# Joystick_Board.net
KiCad netlist of a schematic drawn in Altium Designer
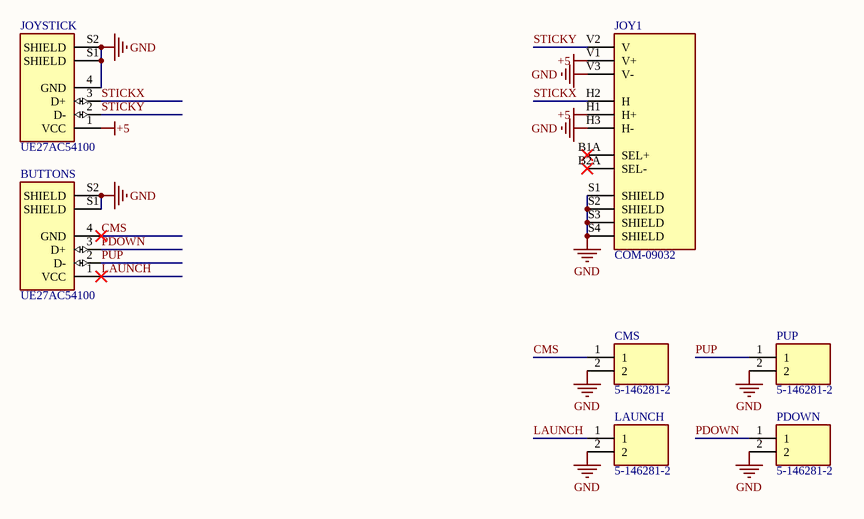
[diagram p0: Joystick Board.SchDoc]

(export (version "E")
  (design (tool "Eeschema 10.0.6"))
  (components
    (comp (ref "BUTTONS")
      (value "UE27AC54100")
      (footprint "AMPHENOL_UE27AC54100")
      (description "USB-A _USB TYPE-A_ USB 2.0 Receptacle Connector 4 Position Through Hole, Right Angle")
      (fields
        (field (name "MF") "Amphenol ICC _Commercial Products_")
        (field (name "DIGI-KEY_PART_NUMBER") "UE27AC54100-ND")
      )
      (libsource (lib "UE27AC54100") (part "UE27AC54100"))
    )
    (comp (ref "CMS")
      (value "5-146281-2")
      (footprint "TE_5-146281-2")
      (description "Header; Breakaway; 0.100 in.; PC Board; Single; 2; 0.025 in.; 0.12 in.; 3 A")
      (fields (field (name "MF") "TE Connectivity"))
      (libsource (lib "5-146281-2") (part "5-146281-2"))
    )
    (comp (ref "JOY1")
      (value "COM-09032")
      (footprint "XDCR_COM-09032")
      (description "Thumb Joystick")
      (libsource (lib "COM-09032") (part "COM-09032"))
    )
    (comp (ref "JOYSTICK")
      (value "UE27AC54100")
      (footprint "AMPHENOL_UE27AC54100")
      (description "USB-A _USB TYPE-A_ USB 2.0 Receptacle Connector 4 Position Through Hole, Right Angle")
      (fields
        (field (name "MF") "Amphenol ICC _Commercial Products_")
        (field (name "DIGI-KEY_PART_NUMBER") "UE27AC54100-ND")
      )
      (libsource (lib "UE27AC54100") (part "UE27AC54100"))
    )
    (comp (ref "LAUNCH")
      (value "5-146281-2")
      (footprint "TE_5-146281-2")
      (description "Header; Breakaway; 0.100 in.; PC Board; Single; 2; 0.025 in.; 0.12 in.; 3 A")
      (fields (field (name "MF") "TE Connectivity"))
      (libsource (lib "5-146281-2") (part "5-146281-2"))
    )
    (comp (ref "PDOWN")
      (value "5-146281-2")
      (footprint "TE_5-146281-2")
      (description "Header; Breakaway; 0.100 in.; PC Board; Single; 2; 0.025 in.; 0.12 in.; 3 A")
      (fields (field (name "MF") "TE Connectivity"))
      (libsource (lib "5-146281-2") (part "5-146281-2"))
    )
    (comp (ref "PUP")
      (value "5-146281-2")
      (footprint "TE_5-146281-2")
      (description "Header; Breakaway; 0.100 in.; PC Board; Single; 2; 0.025 in.; 0.12 in.; 3 A")
      (fields (field (name "MF") "TE Connectivity"))
      (libsource (lib "5-146281-2") (part "5-146281-2"))
    )
  )
  (nets
    (net (code "1") (name "+5") (class "Default")
      (node (ref "JOY1") (pin "H1") (pinfunction "H+_H1") (pintype "passive"))
      (node (ref "JOY1") (pin "V1") (pinfunction "V+_V1") (pintype "passive"))
      (node (ref "JOYSTICK") (pin "1") (pinfunction "VCC_1") (pintype "power_in"))
    )
    (net (code "2") (name "/CMS") (class "Default")
      (node (ref "BUTTONS") (pin "4") (pinfunction "GND_4") (pintype "power_in"))
      (node (ref "CMS") (pin "1") (pinfunction "1_1") (pintype "passive"))
    )
    (net (code "3") (name "/LAUNCH") (class "Default")
      (node (ref "BUTTONS") (pin "1") (pinfunction "VCC_1") (pintype "power_in"))
      (node (ref "LAUNCH") (pin "1") (pinfunction "1_1") (pintype "passive"))
    )
    (net (code "4") (name "/PDOWN") (class "Default")
      (node (ref "BUTTONS") (pin "3") (pinfunction "D+_3") (pintype "bidirectional"))
      (node (ref "PDOWN") (pin "1") (pinfunction "1_1") (pintype "passive"))
    )
    (net (code "5") (name "/PUP") (class "Default")
      (node (ref "BUTTONS") (pin "2") (pinfunction "D-_2") (pintype "bidirectional"))
      (node (ref "PUP") (pin "1") (pinfunction "1_1") (pintype "passive"))
    )
    (net (code "6") (name "/STICKX") (class "Default")
      (node (ref "JOY1") (pin "H2") (pinfunction "H_H2") (pintype "passive"))
      (node (ref "JOYSTICK") (pin "3") (pinfunction "D+_3") (pintype "bidirectional"))
    )
    (net (code "7") (name "/STICKY") (class "Default")
      (node (ref "JOY1") (pin "V2") (pinfunction "V_V2") (pintype "passive"))
      (node (ref "JOYSTICK") (pin "2") (pinfunction "D-_2") (pintype "bidirectional"))
    )
    (net (code "8") (name "GND") (class "Default")
      (node (ref "BUTTONS") (pin "S1") (pinfunction "SHIELD_S1") (pintype "passive"))
      (node (ref "BUTTONS") (pin "S2") (pinfunction "SHIELD_S2") (pintype "passive"))
      (node (ref "CMS") (pin "2") (pinfunction "2_2") (pintype "passive"))
      (node (ref "JOY1") (pin "H3") (pinfunction "H-_H3") (pintype "passive"))
      (node (ref "JOY1") (pin "S1") (pinfunction "SHIELD_S1") (pintype "passive"))
      (node (ref "JOY1") (pin "S2") (pinfunction "SHIELD_S2") (pintype "passive"))
      (node (ref "JOY1") (pin "S3") (pinfunction "SHIELD_S3") (pintype "passive"))
      (node (ref "JOY1") (pin "S4") (pinfunction "SHIELD_S4") (pintype "passive"))
      (node (ref "JOY1") (pin "V3") (pinfunction "V-_V3") (pintype "passive"))
      (node (ref "JOYSTICK") (pin "4") (pinfunction "GND_4") (pintype "power_in"))
      (node (ref "JOYSTICK") (pin "S1") (pinfunction "SHIELD_S1") (pintype "passive"))
      (node (ref "JOYSTICK") (pin "S2") (pinfunction "SHIELD_S2") (pintype "passive"))
      (node (ref "LAUNCH") (pin "2") (pinfunction "2_2") (pintype "passive"))
      (node (ref "PDOWN") (pin "2") (pinfunction "2_2") (pintype "passive"))
      (node (ref "PUP") (pin "2") (pinfunction "2_2") (pintype "passive"))
    )
    (net (code "9") (name "unconnected-(JOY1-SEL+-PadB1A)") (class "Default")
      (node (ref "JOY1") (pin "B1A") (pinfunction "SEL+_B1A") (pintype "passive+no_connect"))
    )
    (net (code "10") (name "unconnected-(JOY1-SEL--PadB2A)") (class "Default")
      (node (ref "JOY1") (pin "B2A") (pinfunction "SEL-_B2A") (pintype "passive+no_connect"))
    )
  )
)
